# V3.net
KiCad netlist of a schematic drawn in Altium Designer
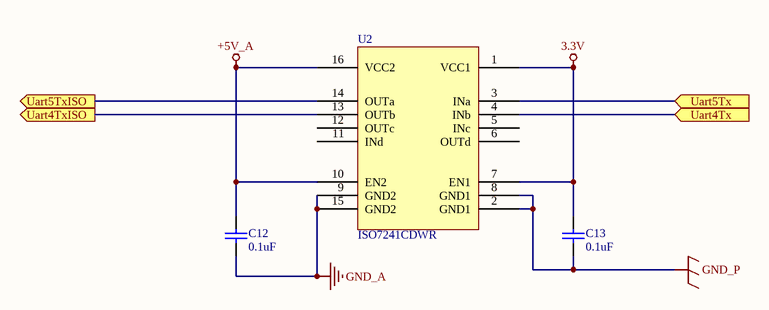
[diagram p0: 海关全向本体电路板V3_通信隔离.SchDoc]

(export (version "E")
  (design (tool "Eeschema 10.0.6"))
  (components
    (comp (ref "C12") (value "0.1uF") (footprint "C0603-S") (libsource (lib "SMD") (part "Cap Semi")))
    (comp (ref "C13") (value "0.1uF") (footprint "C0603-S") (libsource (lib "SMD") (part "Cap Semi")))
    (comp (ref "U2")
      (value "ISO7241CDWR")
      (footprint "SO16-290")
      (description "Octal bus transceiver and 3.3V to 5V shifter with 3-state outputs")
      (libsource (lib "Logic Class") (part "ISO7241A"))
    )
  )
  (nets
    (net (code "1") (name "+5V_A") (class "Default")
      (node (ref "C12") (pin "2") (pinfunction "2_2") (pintype "passive"))
      (node (ref "U2") (pin "10") (pinfunction "EN2_10") (pintype "passive"))
      (node (ref "U2") (pin "16") (pinfunction "VCC2_16") (pintype "passive"))
    )
    (net (code "2") (name "/Uart4Tx") (class "Default")
      (node (ref "U2") (pin "4") (pinfunction "INb_4") (pintype "passive"))
    )
    (net (code "3") (name "/Uart4TxISO") (class "Default")
      (node (ref "U2") (pin "13") (pinfunction "OUTb_13") (pintype "passive"))
    )
    (net (code "4") (name "/Uart5Tx") (class "Default")
      (node (ref "U2") (pin "3") (pinfunction "INa_3") (pintype "passive"))
    )
    (net (code "5") (name "/Uart5TxISO") (class "Default")
      (node (ref "U2") (pin "14") (pinfunction "OUTa_14") (pintype "passive"))
    )
    (net (code "6") (name "3.3V") (class "Default")
      (node (ref "C13") (pin "2") (pinfunction "2_2") (pintype "passive"))
      (node (ref "U2") (pin "1") (pinfunction "VCC1_1") (pintype "passive"))
      (node (ref "U2") (pin "7") (pinfunction "EN1_7") (pintype "passive"))
    )
    (net (code "7") (name "GND_A") (class "Default")
      (node (ref "C12") (pin "1") (pinfunction "1_1") (pintype "passive"))
      (node (ref "U2") (pin "15") (pinfunction "GND2_15") (pintype "passive"))
      (node (ref "U2") (pin "9") (pinfunction "GND2_9") (pintype "passive"))
    )
    (net (code "8") (name "GND_P") (class "Default")
      (node (ref "C13") (pin "1") (pinfunction "1_1") (pintype "passive"))
      (node (ref "U2") (pin "2") (pinfunction "GND1_2") (pintype "passive"))
      (node (ref "U2") (pin "8") (pinfunction "GND1_8") (pintype "passive"))
    )
    (net (code "9") (name "unconnected-(U2-INc-Pad5)") (class "Default")
      (node (ref "U2") (pin "5") (pinfunction "INc_5") (pintype "passive"))
    )
    (net (code "10") (name "unconnected-(U2-INd-Pad11)") (class "Default")
      (node (ref "U2") (pin "11") (pinfunction "INd_11") (pintype "passive"))
    )
    (net (code "11") (name "unconnected-(U2-OUTc-Pad12)") (class "Default")
      (node (ref "U2") (pin "12") (pinfunction "OUTc_12") (pintype "passive"))
    )
    (net (code "12") (name "unconnected-(U2-OUTd-Pad6)") (class "Default")
      (node (ref "U2") (pin "6") (pinfunction "OUTd_6") (pintype "passive"))
    )
  )
)
